# Connector.net
KiCad netlist of a schematic drawn in Altium Designer
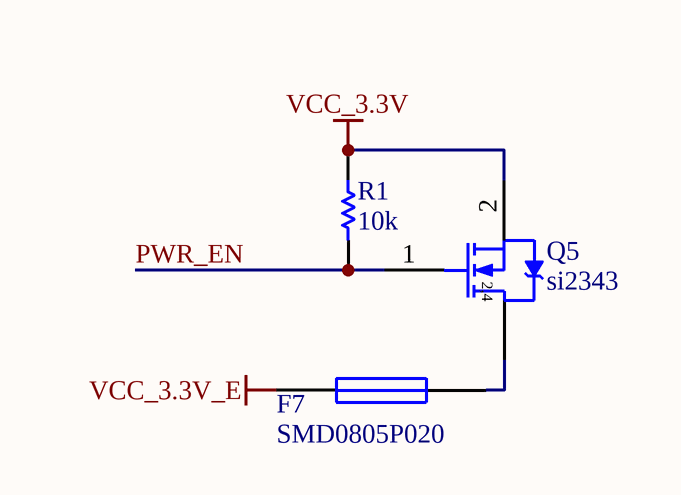
[diagram p0: Connector.SchDoc]

(export (version "E")
  (design (tool "Eeschema 10.0.6"))
  (components
    (comp (ref "F7")
      (value "SMD0805P020")
      (footprint "0805R")
      (description "Fuse")
      (fields (field (name "PUBLISHER") "Altium Limited"))
      (libsource (lib "Miscellaneous Devices") (part "Fuse 1"))
    )
    (comp (ref "Q5")
      (value "si2343")
      (footprint "SOT23-3")
      (description "BUK92150-55A")
      (fields (field (name "PUBLISHER") "Altium Limited"))
      (libsource (lib "Schlib1") (part "BUK92150-55A"))
    )
    (comp (ref "R1")
      (value "10k")
      (footprint "0603r")
      (description "Resistor")
      (fields (field (name "PUBLISHER") "Altium Limited"))
      (libsource (lib "Miscellaneous Devices") (part "Res1"))
    )
  )
  (nets
    (net (code "1") (name "/PWR_EN") (class "Default")
      (node (ref "Q5") (pin "1") (pinfunction "G_1") (pintype "passive"))
      (node (ref "R1") (pin "2") (pinfunction "2_2") (pintype "passive"))
    )
    (net (code "2") (name "Net-(Q5-D)") (class "Default")
      (node (ref "F7") (pin "2") (pinfunction "2_2") (pintype "passive"))
      (node (ref "Q5") (pin "3") (pinfunction "D_3") (pintype "passive"))
    )
    (net (code "3") (name "VCC_3.3V") (class "Default")
      (node (ref "Q5") (pin "2") (pinfunction "S_2") (pintype "passive"))
      (node (ref "R1") (pin "1") (pinfunction "1_1") (pintype "passive"))
    )
    (net (code "4") (name "VCC_3.3V_E") (class "Default")
      (node (ref "F7") (pin "1") (pinfunction "1_1") (pintype "passive"))
    )
  )
)
